# hayaoshi.net
KiCad netlist of a schematic drawn in EAGLE
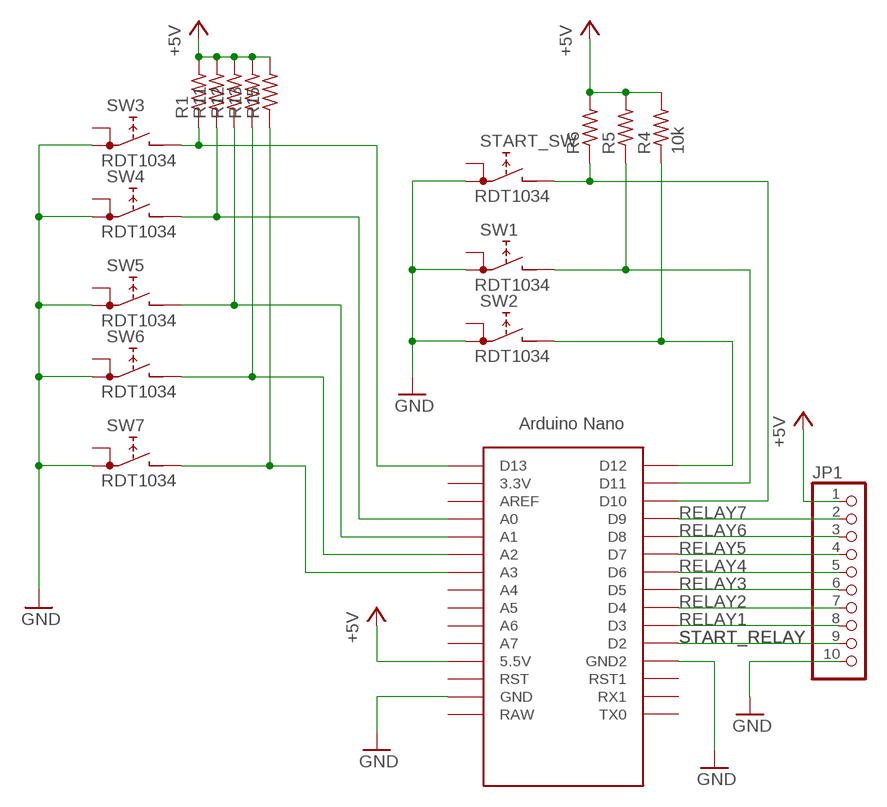
[diagram p0: schematic, sheet 1]

(export (version "E")
  (design (tool "Eeschema 10.0.6"))
  (components
    (comp (ref "JP1")
      (value "PINHD-1X10")
      (footprint "eagle-import:1X10")
      (libsource (lib "eagle-import") (part "PINHD-1X10"))
    )
    (comp (ref "R1")
      (value "R-US_0207/10")
      (footprint "eagle-import:0207_10")
      (libsource (lib "eagle-import") (part "R-US_0207/10"))
    )
    (comp (ref "R4")
      (value "10k")
      (footprint "eagle-import:0207_10")
      (libsource (lib "eagle-import") (part "R-US_0207/10"))
    )
    (comp (ref "R5")
      (value "R-US_0207/10")
      (footprint "eagle-import:0207_10")
      (libsource (lib "eagle-import") (part "R-US_0207/10"))
    )
    (comp (ref "R6")
      (value "R-US_0207/10")
      (footprint "eagle-import:0207_10")
      (libsource (lib "eagle-import") (part "R-US_0207/10"))
    )
    (comp (ref "R11")
      (value "R-US_0207/10")
      (footprint "eagle-import:0207_10")
      (libsource (lib "eagle-import") (part "R-US_0207/10"))
    )
    (comp (ref "R12")
      (value "R-US_0207/10")
      (footprint "eagle-import:0207_10")
      (libsource (lib "eagle-import") (part "R-US_0207/10"))
    )
    (comp (ref "R13")
      (value "R-US_0207/10")
      (footprint "eagle-import:0207_10")
      (libsource (lib "eagle-import") (part "R-US_0207/10"))
    )
    (comp (ref "R15")
      (value "R-US_0207/10")
      (footprint "eagle-import:0207_10")
      (libsource (lib "eagle-import") (part "R-US_0207/10"))
    )
    (comp (ref "START_SW")
      (value "RDT1034")
      (footprint "eagle-import:RDT1034")
      (libsource (lib "eagle-import") (part "RDT1034"))
    )
    (comp (ref "SW1")
      (value "RDT1034")
      (footprint "eagle-import:RDT1034")
      (libsource (lib "eagle-import") (part "RDT1034"))
    )
    (comp (ref "SW2")
      (value "RDT1034")
      (footprint "eagle-import:RDT1034")
      (libsource (lib "eagle-import") (part "RDT1034"))
    )
    (comp (ref "SW3")
      (value "RDT1034")
      (footprint "eagle-import:RDT1034")
      (libsource (lib "eagle-import") (part "RDT1034"))
    )
    (comp (ref "SW4")
      (value "RDT1034")
      (footprint "eagle-import:RDT1034")
      (libsource (lib "eagle-import") (part "RDT1034"))
    )
    (comp (ref "SW5")
      (value "RDT1034")
      (footprint "eagle-import:RDT1034")
      (libsource (lib "eagle-import") (part "RDT1034"))
    )
    (comp (ref "SW6")
      (value "RDT1034")
      (footprint "eagle-import:RDT1034")
      (libsource (lib "eagle-import") (part "RDT1034"))
    )
    (comp (ref "SW7")
      (value "RDT1034")
      (footprint "eagle-import:RDT1034")
      (libsource (lib "eagle-import") (part "RDT1034"))
    )
    (comp (ref "U$1")
      (value "NANO")
      (footprint "eagle-import:NANO")
      (libsource (lib "eagle-import") (part "NANO"))
    )
  )
  (nets
    (net (code "1") (name "+5V") (class "Default")
      (node (ref "JP1") (pin "1") (pinfunction "1_1") (pintype "passive"))
      (node (ref "R1") (pin "2") (pinfunction "2_2") (pintype "passive"))
      (node (ref "R11") (pin "2") (pinfunction "2_2") (pintype "passive"))
      (node (ref "R12") (pin "2") (pinfunction "2_2") (pintype "passive"))
      (node (ref "R13") (pin "2") (pinfunction "2_2") (pintype "passive"))
      (node (ref "R15") (pin "2") (pinfunction "2_2") (pintype "passive"))
      (node (ref "R4") (pin "2") (pinfunction "2_2") (pintype "passive"))
      (node (ref "R5") (pin "2") (pinfunction "2_2") (pintype "passive"))
      (node (ref "R6") (pin "2") (pinfunction "2_2") (pintype "passive"))
      (node (ref "U$1") (pin "5V") (pinfunction "5.5V_5V") (pintype "bidirectional"))
    )
    (net (code "2") (name "/RELAY1") (class "Default")
      (node (ref "JP1") (pin "8") (pinfunction "8_8") (pintype "passive"))
      (node (ref "U$1") (pin "D3") (pinfunction "D3_D3") (pintype "bidirectional"))
    )
    (net (code "3") (name "/RELAY2") (class "Default")
      (node (ref "JP1") (pin "7") (pinfunction "7_7") (pintype "passive"))
      (node (ref "U$1") (pin "D4") (pinfunction "D4_D4") (pintype "bidirectional"))
    )
    (net (code "4") (name "/RELAY3") (class "Default")
      (node (ref "JP1") (pin "6") (pinfunction "6_6") (pintype "passive"))
      (node (ref "U$1") (pin "D5") (pinfunction "D5_D5") (pintype "bidirectional"))
    )
    (net (code "5") (name "/RELAY4") (class "Default")
      (node (ref "JP1") (pin "5") (pinfunction "5_5") (pintype "passive"))
      (node (ref "U$1") (pin "D6") (pinfunction "D6_D6") (pintype "bidirectional"))
    )
    (net (code "6") (name "/RELAY5") (class "Default")
      (node (ref "JP1") (pin "4") (pinfunction "4_4") (pintype "passive"))
      (node (ref "U$1") (pin "D7") (pinfunction "D7_D7") (pintype "bidirectional"))
    )
    (net (code "7") (name "/RELAY6") (class "Default")
      (node (ref "JP1") (pin "3") (pinfunction "3_3") (pintype "passive"))
      (node (ref "U$1") (pin "D8") (pinfunction "D8_D8") (pintype "bidirectional"))
    )
    (net (code "8") (name "/RELAY7") (class "Default")
      (node (ref "JP1") (pin "2") (pinfunction "2_2") (pintype "passive"))
      (node (ref "U$1") (pin "D9") (pinfunction "D9_D9") (pintype "bidirectional"))
    )
    (net (code "9") (name "/START_RELAY") (class "Default")
      (node (ref "JP1") (pin "9") (pinfunction "9_9") (pintype "passive"))
      (node (ref "U$1") (pin "D2") (pinfunction "D2_D2") (pintype "bidirectional"))
    )
    (net (code "10") (name "GND") (class "Default")
      (node (ref "JP1") (pin "10") (pinfunction "10_10") (pintype "passive"))
      (node (ref "START_SW") (pin "A1") (pinfunction "A1_A1") (pintype "passive"))
      (node (ref "SW1") (pin "A1") (pinfunction "A1_A1") (pintype "passive"))
      (node (ref "SW2") (pin "A1") (pinfunction "A1_A1") (pintype "passive"))
      (node (ref "SW3") (pin "A1") (pinfunction "A1_A1") (pintype "passive"))
      (node (ref "SW4") (pin "A1") (pinfunction "A1_A1") (pintype "passive"))
      (node (ref "SW5") (pin "A1") (pinfunction "A1_A1") (pintype "passive"))
      (node (ref "SW6") (pin "A1") (pinfunction "A1_A1") (pintype "passive"))
      (node (ref "SW7") (pin "A1") (pinfunction "A1_A1") (pintype "passive"))
      (node (ref "U$1") (pin "GND") (pinfunction "GND_GND") (pintype "bidirectional"))
      (node (ref "U$1") (pin "GND1") (pinfunction "GND2_GND1") (pintype "bidirectional"))
    )
    (net (code "11") (name "Net-(R1-Pad1)") (class "Default")
      (node (ref "R1") (pin "1") (pinfunction "1_1") (pintype "passive"))
      (node (ref "SW3") (pin "B") (pinfunction "B_B") (pintype "passive"))
      (node (ref "U$1") (pin "D13") (pinfunction "D13_D13") (pintype "bidirectional"))
    )
    (net (code "12") (name "Net-(R4-Pad1)") (class "Default")
      (node (ref "R4") (pin "1") (pinfunction "1_1") (pintype "passive"))
      (node (ref "SW2") (pin "B") (pinfunction "B_B") (pintype "passive"))
      (node (ref "U$1") (pin "D12") (pinfunction "D12_D12") (pintype "bidirectional"))
    )
    (net (code "13") (name "Net-(R5-Pad1)") (class "Default")
      (node (ref "R5") (pin "1") (pinfunction "1_1") (pintype "passive"))
      (node (ref "SW1") (pin "B") (pinfunction "B_B") (pintype "passive"))
      (node (ref "U$1") (pin "D11") (pinfunction "D11_D11") (pintype "bidirectional"))
    )
    (net (code "14") (name "Net-(R6-Pad1)") (class "Default")
      (node (ref "R6") (pin "1") (pinfunction "1_1") (pintype "passive"))
      (node (ref "START_SW") (pin "B") (pinfunction "B_B") (pintype "passive"))
      (node (ref "U$1") (pin "D10") (pinfunction "D10_D10") (pintype "bidirectional"))
    )
    (net (code "15") (name "Net-(R11-Pad1)") (class "Default")
      (node (ref "R11") (pin "1") (pinfunction "1_1") (pintype "passive"))
      (node (ref "SW4") (pin "B") (pinfunction "B_B") (pintype "passive"))
      (node (ref "U$1") (pin "A0") (pinfunction "A0_A0") (pintype "bidirectional"))
    )
    (net (code "16") (name "Net-(R12-Pad1)") (class "Default")
      (node (ref "R12") (pin "1") (pinfunction "1_1") (pintype "passive"))
      (node (ref "SW5") (pin "B") (pinfunction "B_B") (pintype "passive"))
      (node (ref "U$1") (pin "A1") (pinfunction "A1_A1") (pintype "bidirectional"))
    )
    (net (code "17") (name "Net-(R13-Pad1)") (class "Default")
      (node (ref "R13") (pin "1") (pinfunction "1_1") (pintype "passive"))
      (node (ref "SW6") (pin "B") (pinfunction "B_B") (pintype "passive"))
      (node (ref "U$1") (pin "A2") (pinfunction "A2_A2") (pintype "bidirectional"))
    )
    (net (code "18") (name "Net-(R15-Pad1)") (class "Default")
      (node (ref "R15") (pin "1") (pinfunction "1_1") (pintype "passive"))
      (node (ref "SW7") (pin "B") (pinfunction "B_B") (pintype "passive"))
      (node (ref "U$1") (pin "A3") (pinfunction "A3_A3") (pintype "bidirectional"))
    )
    (net (code "19") (name "unconnected-(START_SW-PadA)") (class "Default")
      (node (ref "START_SW") (pin "A") (pinfunction "A_A") (pintype "passive"))
    )
    (net (code "20") (name "unconnected-(SW1-PadA)") (class "Default")
      (node (ref "SW1") (pin "A") (pinfunction "A_A") (pintype "passive"))
    )
    (net (code "21") (name "unconnected-(SW2-PadA)") (class "Default")
      (node (ref "SW2") (pin "A") (pinfunction "A_A") (pintype "passive"))
    )
    (net (code "22") (name "unconnected-(SW3-PadA)") (class "Default")
      (node (ref "SW3") (pin "A") (pinfunction "A_A") (pintype "passive"))
    )
    (net (code "23") (name "unconnected-(SW4-PadA)") (class "Default")
      (node (ref "SW4") (pin "A") (pinfunction "A_A") (pintype "passive"))
    )
    (net (code "24") (name "unconnected-(SW5-PadA)") (class "Default")
      (node (ref "SW5") (pin "A") (pinfunction "A_A") (pintype "passive"))
    )
    (net (code "25") (name "unconnected-(SW6-PadA)") (class "Default")
      (node (ref "SW6") (pin "A") (pinfunction "A_A") (pintype "passive"))
    )
    (net (code "26") (name "unconnected-(SW7-PadA)") (class "Default")
      (node (ref "SW7") (pin "A") (pinfunction "A_A") (pintype "passive"))
    )
    (net (code "27") (name "unconnected-(U$1-Pad3.3V)") (class "Default")
      (node (ref "U$1") (pin "3.3V") (pinfunction "3.3V_3.3V") (pintype "bidirectional"))
    )
    (net (code "28") (name "unconnected-(U$1-PadA4)") (class "Default")
      (node (ref "U$1") (pin "A4") (pinfunction "A4_A4") (pintype "bidirectional"))
    )
    (net (code "29") (name "unconnected-(U$1-PadA5)") (class "Default")
      (node (ref "U$1") (pin "A5") (pinfunction "A5_A5") (pintype "bidirectional"))
    )
    (net (code "30") (name "unconnected-(U$1-PadA6)") (class "Default")
      (node (ref "U$1") (pin "A6") (pinfunction "A6_A6") (pintype "bidirectional"))
    )
    (net (code "31") (name "unconnected-(U$1-PadA7)") (class "Default")
      (node (ref "U$1") (pin "A7") (pinfunction "A7_A7") (pintype "bidirectional"))
    )
    (net (code "32") (name "unconnected-(U$1-PadAREF)") (class "Default")
      (node (ref "U$1") (pin "AREF") (pinfunction "AREF_AREF") (pintype "bidirectional"))
    )
    (net (code "33") (name "unconnected-(U$1-PadICSP1)") (class "Default")
      (node (ref "U$1") (pin "ICSP1") (pinfunction "ICSP1_ICSP1") (pintype "bidirectional"))
    )
    (net (code "34") (name "unconnected-(U$1-PadICSP2)") (class "Default")
      (node (ref "U$1") (pin "ICSP2") (pinfunction "ICSP2_ICSP2") (pintype "bidirectional"))
    )
    (net (code "35") (name "unconnected-(U$1-PadICSP3)") (class "Default")
      (node (ref "U$1") (pin "ICSP3") (pinfunction "ICSP3_ICSP3") (pintype "bidirectional"))
    )
    (net (code "36") (name "unconnected-(U$1-PadICSP4)") (class "Default")
      (node (ref "U$1") (pin "ICSP4") (pinfunction "ICSP4_ICSP4") (pintype "bidirectional"))
    )
    (net (code "37") (name "unconnected-(U$1-PadICSP5)") (class "Default")
      (node (ref "U$1") (pin "ICSP5") (pinfunction "ICSP5_ICSP5") (pintype "bidirectional"))
    )
    (net (code "38") (name "unconnected-(U$1-PadICSP6)") (class "Default")
      (node (ref "U$1") (pin "ICSP6") (pinfunction "ICSP6_ICSP6") (pintype "bidirectional"))
    )
    (net (code "39") (name "unconnected-(U$1-PadRAW)") (class "Default")
      (node (ref "U$1") (pin "RAW") (pinfunction "RAW_RAW") (pintype "bidirectional"))
    )
    (net (code "40") (name "unconnected-(U$1-PadRST)") (class "Default")
      (node (ref "U$1") (pin "RST") (pinfunction "RST_RST") (pintype "bidirectional"))
    )
    (net (code "41") (name "unconnected-(U$1-PadRST1)") (class "Default")
      (node (ref "U$1") (pin "RST1") (pinfunction "RST1_RST1") (pintype "bidirectional"))
    )
    (net (code "42") (name "unconnected-(U$1-PadRX1)") (class "Default")
      (node (ref "U$1") (pin "RX1") (pinfunction "RX1_RX1") (pintype "bidirectional"))
    )
    (net (code "43") (name "unconnected-(U$1-PadTX0)") (class "Default")
      (node (ref "U$1") (pin "TX0") (pinfunction "TX0_TX0") (pintype "bidirectional"))
    )
  )
)
